# LeoBlinky2018.net
KiCad netlist of a schematic drawn in Altium Designer
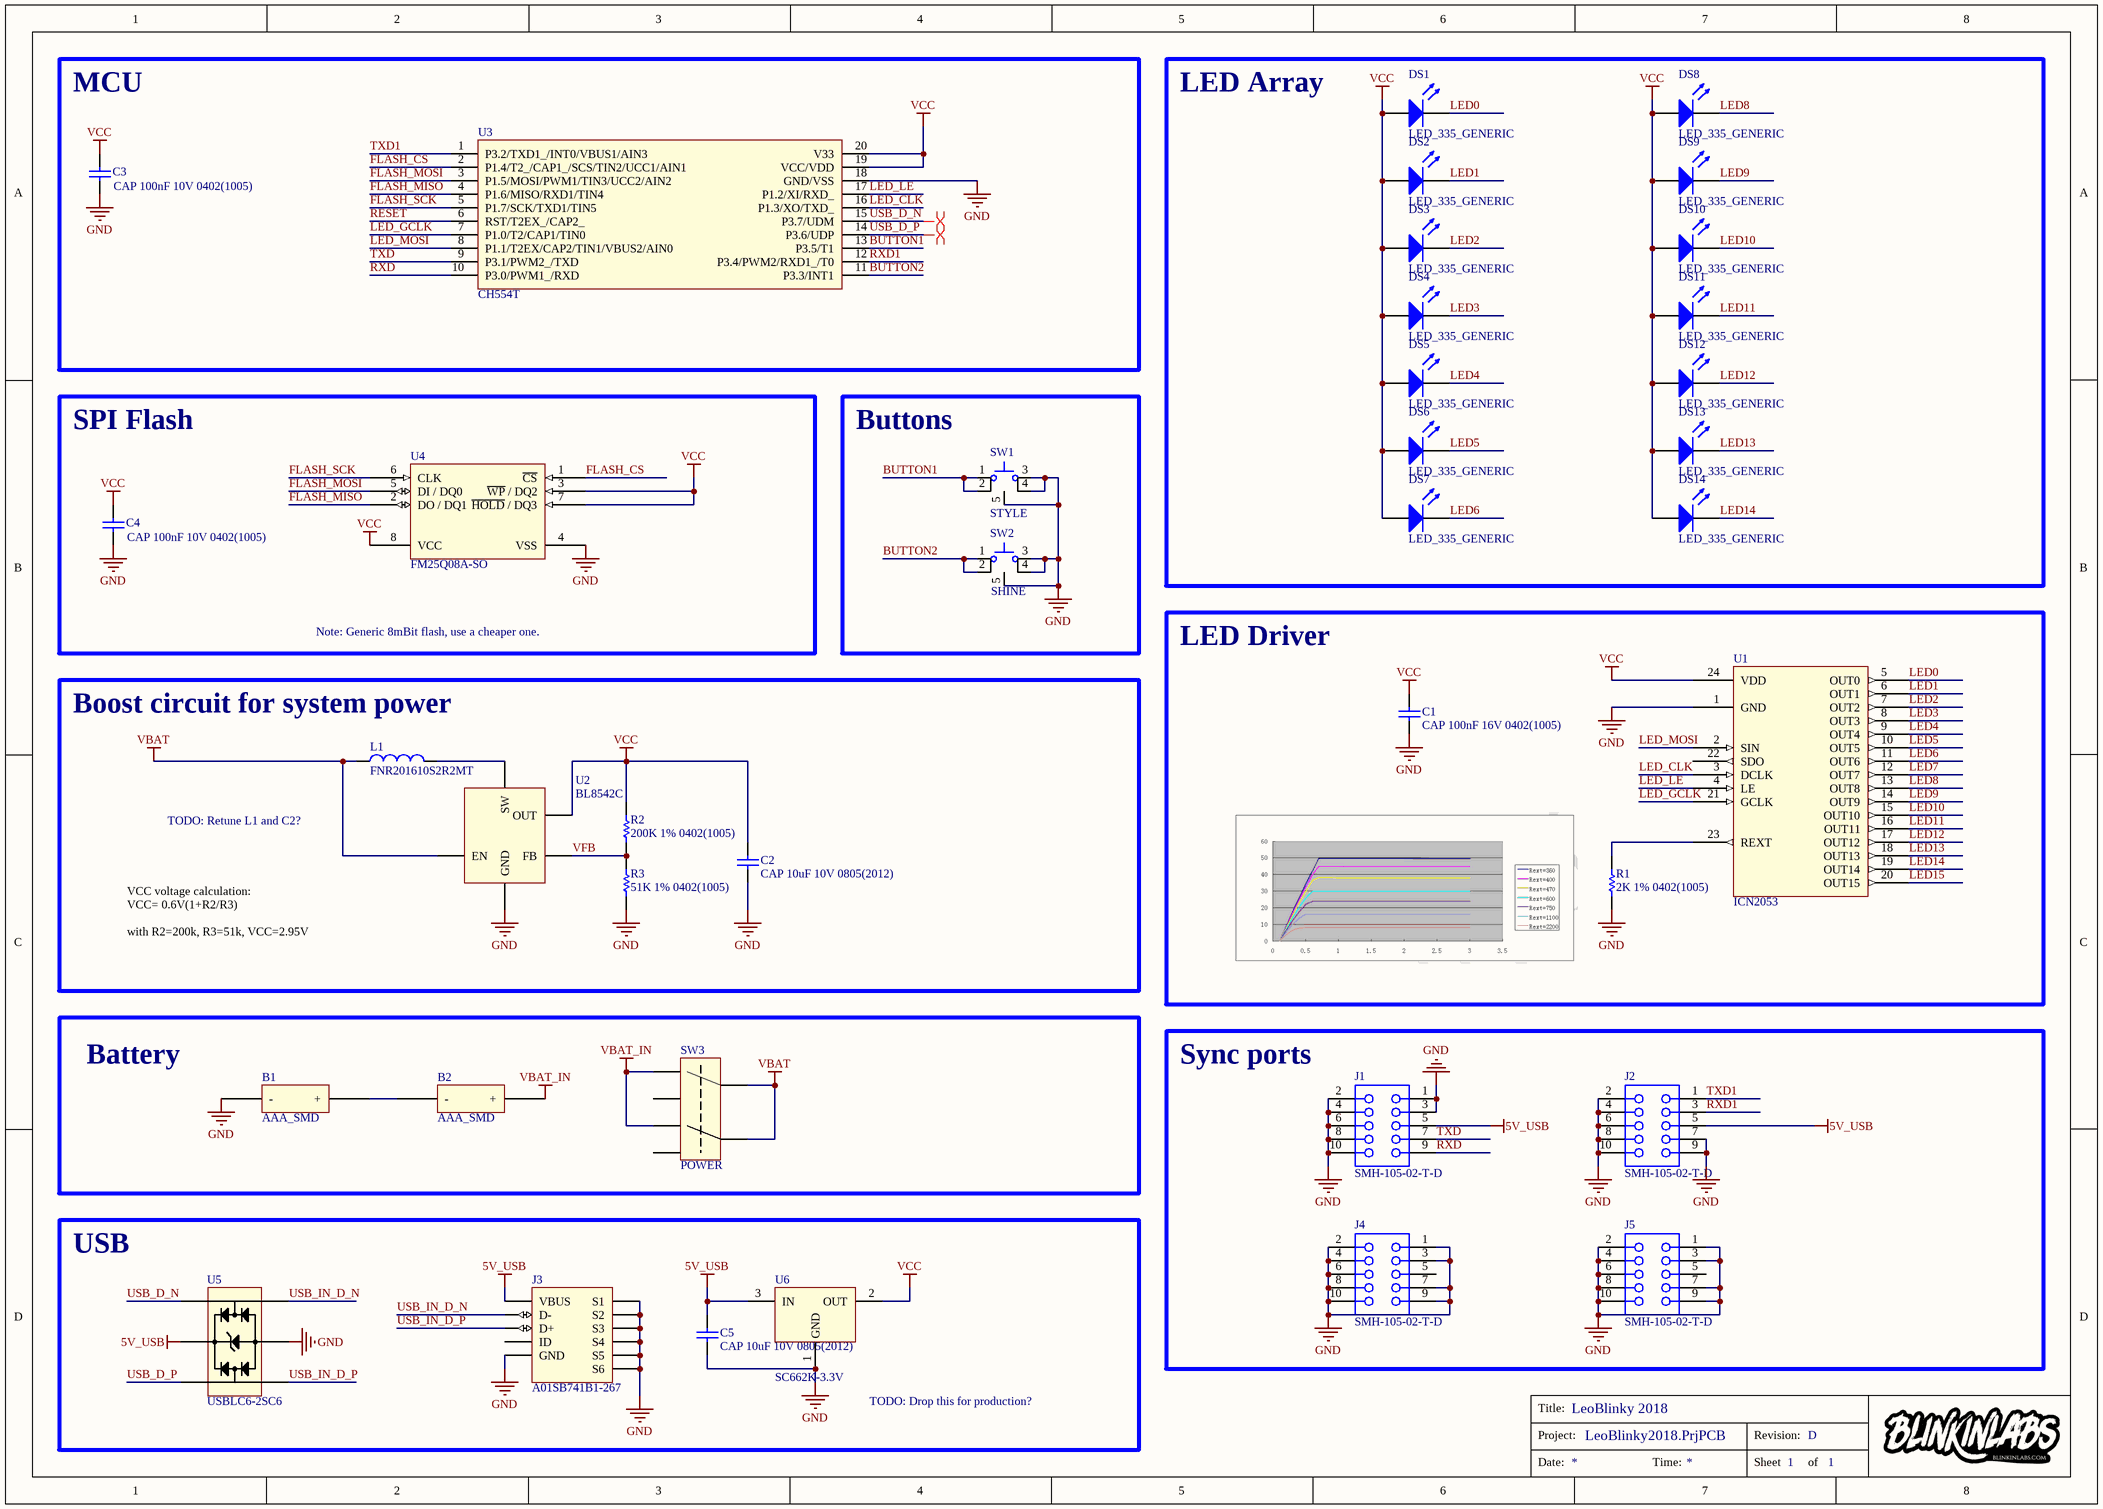
[diagram p0: LeoBlinky2018.SchDoc]

(export (version "E")
  (design (tool "Eeschema 10.0.6"))
  (components
    (comp (ref "B1")
      (value "AAA_SMD")
      (footprint "AAA_SMD")
      (description "AAA battery holder, surface mount.")
      (libsource (lib "Blinkinlabs") (part "AAA_SMD"))
    )
    (comp (ref "B2")
      (value "AAA_SMD")
      (footprint "AAA_SMD")
      (description "AAA battery holder, surface mount.")
      (libsource (lib "Blinkinlabs") (part "AAA_SMD"))
    )
    (comp (ref "C1")
      (value "CAP 100nF 16V 0402(1005)")
      (footprint "CAPC0402(1005)60_N")
      (description "CAP 100nF 16V -20% to +80% 0402 (1005 Metric) Thickness 0.6mm SMD")
      (fields (field (name "TOLERANCE") "-20% to +80%"))
      (libsource (lib "Altium Content Vault") (part "CAP"))
    )
    (comp (ref "C2")
      (value "CAP 10uF 10V 0805(2012)")
      (footprint "CAPC0805(2012)145_N")
      (description "CAP 10uF 10V ±10% 0805 (2012 Metric) Thickness 1.45mm SMD")
      (fields (field (name "TOLERANCE") "Â±10%"))
      (libsource (lib "Altium Content Vault") (part "CMP-1036-04922-1"))
    )
    (comp (ref "C3")
      (value "CAP 100nF 10V 0402(1005)")
      (footprint "CAPC0402(1005)60_L")
      (description "CAP 100nF 10V ±10% 0402 (1005 Metric) Thickness 0.6mm SMD")
      (fields (field (name "TOLERANCE") "Â±10%"))
      (libsource (lib "Altium Content Vault") (part "CMP-1034-02065-1"))
    )
    (comp (ref "C4")
      (value "CAP 100nF 10V 0402(1005)")
      (footprint "CAPC0402(1005)60_L")
      (description "CAP 100nF 10V ±10% 0402 (1005 Metric) Thickness 0.6mm SMD")
      (fields (field (name "TOLERANCE") "Â±10%"))
      (libsource (lib "Altium Content Vault") (part "CMP-1034-02065-1"))
    )
    (comp (ref "C5")
      (value "CAP 10uF 10V 0805(2012)")
      (footprint "CAPC0805(2012)145_N")
      (description "CAP 10uF 10V ±10% 0805 (2012 Metric) Thickness 1.45mm SMD")
      (fields (field (name "TOLERANCE") "Â±10%"))
      (libsource (lib "Altium Content Vault") (part "CAP"))
    )
    (comp (ref "DS1")
      (value "LED_335_GENERIC")
      (footprint "LED_335_GENERIC")
      (description "SMD LED, side visible, generic")
      (libsource (lib "Blinkinlabs") (part "LED_335_GENERIC"))
    )
    (comp (ref "DS2")
      (value "LED_335_GENERIC")
      (footprint "LED_335_GENERIC")
      (description "SMD LED, side visible, generic")
      (libsource (lib "Blinkinlabs") (part "LED_335_GENERIC"))
    )
    (comp (ref "DS3")
      (value "LED_335_GENERIC")
      (footprint "LED_335_GENERIC")
      (description "SMD LED, side visible, generic")
      (libsource (lib "Blinkinlabs") (part "LED_335_GENERIC"))
    )
    (comp (ref "DS4")
      (value "LED_335_GENERIC")
      (footprint "LED_335_GENERIC")
      (description "SMD LED, side visible, generic")
      (libsource (lib "Blinkinlabs") (part "LED_335_GENERIC"))
    )
    (comp (ref "DS5")
      (value "LED_335_GENERIC")
      (footprint "LED_335_GENERIC")
      (description "SMD LED, side visible, generic")
      (libsource (lib "Blinkinlabs") (part "LED_335_GENERIC"))
    )
    (comp (ref "DS6")
      (value "LED_335_GENERIC")
      (footprint "LED_335_GENERIC")
      (description "SMD LED, side visible, generic")
      (libsource (lib "Blinkinlabs") (part "LED_335_GENERIC"))
    )
    (comp (ref "DS7")
      (value "LED_335_GENERIC")
      (footprint "LED_335_GENERIC")
      (description "SMD LED, side visible, generic")
      (libsource (lib "Blinkinlabs") (part "LED_335_GENERIC"))
    )
    (comp (ref "DS8")
      (value "LED_335_GENERIC")
      (footprint "LED_335_GENERIC")
      (description "SMD LED, side visible, generic")
      (libsource (lib "Blinkinlabs") (part "LED_335_GENERIC"))
    )
    (comp (ref "DS9")
      (value "LED_335_GENERIC")
      (footprint "LED_335_GENERIC")
      (description "SMD LED, side visible, generic")
      (libsource (lib "Blinkinlabs") (part "LED_335_GENERIC"))
    )
    (comp (ref "DS10")
      (value "LED_335_GENERIC")
      (footprint "LED_335_GENERIC")
      (description "SMD LED, side visible, generic")
      (libsource (lib "Blinkinlabs") (part "LED_335_GENERIC"))
    )
    (comp (ref "DS11")
      (value "LED_335_GENERIC")
      (footprint "LED_335_GENERIC")
      (description "SMD LED, side visible, generic")
      (libsource (lib "Blinkinlabs") (part "LED_335_GENERIC"))
    )
    (comp (ref "DS12")
      (value "LED_335_GENERIC")
      (footprint "LED_335_GENERIC")
      (description "SMD LED, side visible, generic")
      (libsource (lib "Blinkinlabs") (part "LED_335_GENERIC"))
    )
    (comp (ref "DS13")
      (value "LED_335_GENERIC")
      (footprint "LED_335_GENERIC")
      (description "SMD LED, side visible, generic")
      (libsource (lib "Blinkinlabs") (part "LED_335_GENERIC"))
    )
    (comp (ref "DS14")
      (value "LED_335_GENERIC")
      (footprint "LED_335_GENERIC")
      (description "SMD LED, side visible, generic")
      (libsource (lib "Blinkinlabs") (part "LED_335_GENERIC"))
    )
    (comp (ref "J1")
      (value "SMH-105-02-T-D")
      (footprint "SMTC-SMH-105-02-X-D")
      (description "SMT Horizontal Socket, -55 to 105 degC, 2.54 mm Pitch, 10-Pin, Female, RoHS")
      (fields (field (name "MANUFACTURER") "Samtec"))
      (libsource (lib "Altium Content Vault") (part "SMTC-SMH-105-02-X-D-X"))
    )
    (comp (ref "J2")
      (value "SMH-105-02-T-D")
      (footprint "SMTC-SMH-105-02-X-D")
      (description "SMT Horizontal Socket, -55 to 105 degC, 2.54 mm Pitch, 10-Pin, Female, RoHS")
      (fields (field (name "MANUFACTURER") "Samtec"))
      (libsource (lib "Altium Content Vault") (part "SMTC-SMH-105-02-X-D-X"))
    )
    (comp (ref "J3")
      (value "A01SB741B1-267")
      (footprint "A01SB741B1-267")
      (description "Micro USB B type 四脚全插牛角")
      (libsource (lib "Blinkinlabs") (part "A01SB741B1-267"))
    )
    (comp (ref "J4")
      (value "SMH-105-02-T-D")
      (footprint "SMTC-SMH-105-02-X-D")
      (description "SMT Horizontal Socket, -55 to 105 degC, 2.54 mm Pitch, 10-Pin, Female, RoHS")
      (fields (field (name "MANUFACTURER") "Samtec"))
      (libsource (lib "Altium Content Vault") (part "SMTC-SMH-105-02-X-D-X"))
    )
    (comp (ref "J5")
      (value "SMH-105-02-T-D")
      (footprint "SMTC-SMH-105-02-X-D")
      (description "SMT Horizontal Socket, -55 to 105 degC, 2.54 mm Pitch, 10-Pin, Female, RoHS")
      (fields (field (name "MANUFACTURER") "Samtec"))
      (libsource (lib "Altium Content Vault") (part "SMTC-SMH-105-02-X-D-X"))
    )
    (comp (ref "L1")
      (value "FNR201610S2R2MT")
      (footprint "FNR201610S")
      (description "Wire Wound SMD Power Inductors 2.0×1.6×1.0 2.2uH")
      (libsource (lib "Blinkinlabs") (part "FNR201610S2R2MT"))
    )
    (comp (ref "R1")
      (value "2K 1% 0402(1005)")
      (footprint "RESC0402(1005)_N")
      (description "2K 0.063W 1% 0402 (1005 Metric)  SMD")
      (fields (field (name "POWER") "0.063 W") (field (name "TOLERANCE") "1 %"))
      (libsource (lib "Altium Content Vault") (part "RES"))
    )
    (comp (ref "R2")
      (value "200K 1% 0402(1005)")
      (footprint "RESC0402(1005)_L")
      (description "200K 0.063W 1% 0402 (1005 Metric)  SMD")
      (fields (field (name "TOLERANCE") "1 %") (field (name "POWER") "0.063 W"))
      (libsource (lib "Altium Content Vault") (part "RES"))
    )
    (comp (ref "R3")
      (value "51K 1% 0402(1005)")
      (footprint "RESC0402(1005)_L")
      (description "51K 0.063W 1% 0402 (1005 Metric)  SMD")
      (fields (field (name "TOLERANCE") "1 %") (field (name "POWER") "0.063 W"))
      (libsource (lib "Altium Content Vault") (part "RES"))
    )
    (comp (ref "SW1")
      (value "STYLE")
      (footprint "TD-07XB")
      (description "Tact Switch")
      (fields
        (field (name "MANUFACTURER") "ShenZhen XieJia Electronics Co Ltd")
        (field (name "PARTNUMBER") "TD-07XB")
      )
      (libsource (lib "Blinkinlabs") (part "TD-07XB"))
    )
    (comp (ref "SW2")
      (value "SHINE")
      (footprint "TD-07XB")
      (description "Tact Switch")
      (fields
        (field (name "MANUFACTURER") "ShenZhen XieJia Electronics Co Ltd")
        (field (name "PARTNUMBER") "TD-07XB")
      )
      (libsource (lib "Blinkinlabs") (part "TD-07XB"))
    )
    (comp (ref "SW3")
      (value "POWER")
      (footprint "MSK-1133-NOHOLE")
      (description "SMD micro toggle switch, 2 position, 2 circuit")
      (libsource (lib "Blinkinlabs") (part "MSK-1133"))
    )
    (comp (ref "U1")
      (value "ICN2053")
      (footprint "SOP64P600X175-24N")
      (description "16-Channel PWM Constant Current LED Sink Driver")
      (fields (field (name "MANUFACTURER") "ChipOne"))
      (libsource (lib "Blinkinlabs") (part "ICN2053"))
    )
    (comp (ref "U2")
      (value "BL8542C")
      (footprint "SOT95P280X130-5N")
      (description "0.85V startup, 1MHz, 300mA Iout,  Synchronous Boost Converter (adjustable output)")
      (fields (field (name "MANUFACTURER") "Belling"))
      (libsource (lib "Blinkinlabs") (part "BL8542C"))
    )
    (comp (ref "U3")
      (value "CH554T")
      (footprint "TSOP65P660X110-20N")
      (description "8-bit enhanced USB microcontroller")
      (fields (field (name "MANUFACTURER") "WCH"))
      (libsource (lib "Blinkinlabs") (part "CH554T"))
    )
    (comp (ref "U4")
      (value "FM25Q08A-SO")
      (footprint "SOP127P600X175-8N")
      (description "8M-BIT SERIAL FLASH MEMORY, 150mil width")
      (fields (field (name "MANUFACTURER") "Shanghai Fudan Microelectronics Group Company Limited"))
      (libsource (lib "Blinkinlabs") (part "FM25Q08A-SO"))
    )
    (comp (ref "U5")
      (value "USBLC6-2SC6")
      (footprint "SOT95P280X145-6N")
      (description "Very low capacitance ESD protection")
      (fields (field (name "MANUFACTURER") "STMicroelectronics"))
      (libsource (lib "Blinkinlabs") (part "USBLC6-2SC6"))
    )
    (comp (ref "U6")
      (value "SC662K-3.3V")
      (footprint "SOT95P230X117-3N")
      (description "3.3V, 250mA Low dropout voltage regulator IC")
      (libsource (lib "Blinkinlabs") (part "SC662K-3.3V"))
    )
  )
  (nets
    (net (code "1") (name "/BUTTON1") (class "Default")
      (node (ref "SW1") (pin "1") (pinfunction "1_1") (pintype "passive"))
      (node (ref "SW1") (pin "2") (pinfunction "2_2") (pintype "passive"))
      (node (ref "U3") (pin "13") (pinfunction "P3.5/T1_13") (pintype "passive"))
    )
    (net (code "2") (name "/BUTTON2") (class "Default")
      (node (ref "SW2") (pin "1") (pinfunction "1_1") (pintype "passive"))
      (node (ref "SW2") (pin "2") (pinfunction "2_2") (pintype "passive"))
      (node (ref "U3") (pin "11") (pinfunction "P3.3/INT1_11") (pintype "passive"))
    )
    (net (code "3") (name "/FLASH_CS") (class "Default")
      (node (ref "U3") (pin "2") (pinfunction "P1.4/T2_/CAP1_/SCS/TIN2/UCC1/AIN1_2") (pintype "passive"))
      (node (ref "U4") (pin "1") (pinfunction "~{CS}_1") (pintype "input"))
    )
    (net (code "4") (name "/FLASH_MISO") (class "Default")
      (node (ref "U3") (pin "4") (pinfunction "P1.6/MISO/RXD1/TIN4_4") (pintype "passive"))
      (node (ref "U4") (pin "2") (pinfunction "DO_/_DQ1_2") (pintype "bidirectional"))
    )
    (net (code "5") (name "/FLASH_MOSI") (class "Default")
      (node (ref "U3") (pin "3") (pinfunction "P1.5/MOSI/PWM1/TIN3/UCC2/AIN2_3") (pintype "passive"))
      (node (ref "U4") (pin "5") (pinfunction "DI_/_DQ0_5") (pintype "bidirectional"))
    )
    (net (code "6") (name "/FLASH_SCK") (class "Default")
      (node (ref "U3") (pin "5") (pinfunction "P1.7/SCK/TXD1/TIN5_5") (pintype "passive"))
      (node (ref "U4") (pin "6") (pinfunction "CLK_6") (pintype "input"))
    )
    (net (code "7") (name "/LED0") (class "Default")
      (node (ref "DS1") (pin "1") (pinfunction "1_1") (pintype "passive"))
      (node (ref "U1") (pin "5") (pinfunction "OUT0_5") (pintype "output"))
    )
    (net (code "8") (name "/LED1") (class "Default")
      (node (ref "DS2") (pin "1") (pinfunction "1_1") (pintype "passive"))
      (node (ref "U1") (pin "6") (pinfunction "OUT1_6") (pintype "output"))
    )
    (net (code "9") (name "/LED2") (class "Default")
      (node (ref "DS3") (pin "1") (pinfunction "1_1") (pintype "passive"))
      (node (ref "U1") (pin "7") (pinfunction "OUT2_7") (pintype "output"))
    )
    (net (code "10") (name "/LED3") (class "Default")
      (node (ref "DS4") (pin "1") (pinfunction "1_1") (pintype "passive"))
      (node (ref "U1") (pin "8") (pinfunction "OUT3_8") (pintype "output"))
    )
    (net (code "11") (name "/LED4") (class "Default")
      (node (ref "DS5") (pin "1") (pinfunction "1_1") (pintype "passive"))
      (node (ref "U1") (pin "9") (pinfunction "OUT4_9") (pintype "output"))
    )
    (net (code "12") (name "/LED5") (class "Default")
      (node (ref "DS6") (pin "1") (pinfunction "1_1") (pintype "passive"))
      (node (ref "U1") (pin "10") (pinfunction "OUT5_10") (pintype "output"))
    )
    (net (code "13") (name "/LED6") (class "Default")
      (node (ref "DS7") (pin "1") (pinfunction "1_1") (pintype "passive"))
      (node (ref "U1") (pin "11") (pinfunction "OUT6_11") (pintype "output"))
    )
    (net (code "14") (name "/LED7") (class "Default")
      (node (ref "U1") (pin "12") (pinfunction "OUT7_12") (pintype "output"))
    )
    (net (code "15") (name "/LED8") (class "Default")
      (node (ref "DS8") (pin "1") (pinfunction "1_1") (pintype "passive"))
      (node (ref "U1") (pin "13") (pinfunction "OUT8_13") (pintype "output"))
    )
    (net (code "16") (name "/LED9") (class "Default")
      (node (ref "DS9") (pin "1") (pinfunction "1_1") (pintype "passive"))
      (node (ref "U1") (pin "14") (pinfunction "OUT9_14") (pintype "output"))
    )
    (net (code "17") (name "/LED10") (class "Default")
      (node (ref "DS10") (pin "1") (pinfunction "1_1") (pintype "passive"))
      (node (ref "U1") (pin "15") (pinfunction "OUT10_15") (pintype "output"))
    )
    (net (code "18") (name "/LED11") (class "Default")
      (node (ref "DS11") (pin "1") (pinfunction "1_1") (pintype "passive"))
      (node (ref "U1") (pin "16") (pinfunction "OUT11_16") (pintype "output"))
    )
    (net (code "19") (name "/LED12") (class "Default")
      (node (ref "DS12") (pin "1") (pinfunction "1_1") (pintype "passive"))
      (node (ref "U1") (pin "17") (pinfunction "OUT12_17") (pintype "output"))
    )
    (net (code "20") (name "/LED13") (class "Default")
      (node (ref "DS13") (pin "1") (pinfunction "1_1") (pintype "passive"))
      (node (ref "U1") (pin "18") (pinfunction "OUT13_18") (pintype "output"))
    )
    (net (code "21") (name "/LED14") (class "Default")
      (node (ref "DS14") (pin "1") (pinfunction "1_1") (pintype "passive"))
      (node (ref "U1") (pin "19") (pinfunction "OUT14_19") (pintype "output"))
    )
    (net (code "22") (name "/LED15") (class "Default")
      (node (ref "U1") (pin "20") (pinfunction "OUT15_20") (pintype "output"))
    )
    (net (code "23") (name "/LED_CLK") (class "Default")
      (node (ref "U1") (pin "3") (pinfunction "DCLK_3") (pintype "input"))
      (node (ref "U3") (pin "16") (pinfunction "P1.3/XO/TXD__16") (pintype "passive"))
    )
    (net (code "24") (name "/LED_GCLK") (class "Default")
      (node (ref "U1") (pin "21") (pinfunction "GCLK_21") (pintype "input"))
      (node (ref "U3") (pin "7") (pinfunction "P1.0/T2/CAP1/TIN0_7") (pintype "passive"))
    )
    (net (code "25") (name "/LED_LE") (class "Default")
      (node (ref "U1") (pin "4") (pinfunction "LE_4") (pintype "input"))
      (node (ref "U3") (pin "17") (pinfunction "P1.2/XI/RXD__17") (pintype "passive"))
    )
    (net (code "26") (name "/LED_MOSI") (class "Default")
      (node (ref "U1") (pin "2") (pinfunction "SIN_2") (pintype "input"))
      (node (ref "U3") (pin "8") (pinfunction "P1.1/T2EX/CAP2/TIN1/VBUS2/AIN0_8") (pintype "passive"))
    )
    (net (code "27") (name "/RESET") (class "Default")
      (node (ref "U3") (pin "6") (pinfunction "RST/T2EX_/CAP2__6") (pintype "passive"))
    )
    (net (code "28") (name "/RXD") (class "Default")
      (node (ref "J1") (pin "9") (pinfunction "9_9") (pintype "passive"))
      (node (ref "U3") (pin "10") (pinfunction "P3.0/PWM1_/RXD_10") (pintype "passive"))
    )
    (net (code "29") (name "/RXD1") (class "Default")
      (node (ref "J2") (pin "3") (pinfunction "3_3") (pintype "passive"))
      (node (ref "U3") (pin "12") (pinfunction "P3.4/PWM2/RXD1_/T0_12") (pintype "passive"))
    )
    (net (code "30") (name "/TXD") (class "Default")
      (node (ref "J1") (pin "7") (pinfunction "7_7") (pintype "passive"))
      (node (ref "U3") (pin "9") (pinfunction "P3.1/PWM2_/TXD_9") (pintype "passive"))
    )
    (net (code "31") (name "/TXD1") (class "Default")
      (node (ref "J2") (pin "1") (pinfunction "1_1") (pintype "passive"))
      (node (ref "U3") (pin "1") (pinfunction "P3.2/TXD1_/INT0/VBUS1/AIN3_1") (pintype "passive"))
    )
    (net (code "32") (name "/USB_D_N") (class "Default")
      (node (ref "U3") (pin "15") (pinfunction "P3.7/UDM_15") (pintype "passive"))
      (node (ref "U5") (pin "4") (pinfunction "I/O2_4") (pintype "passive"))
    )
    (net (code "33") (name "/USB_D_P") (class "Default")
      (node (ref "U3") (pin "14") (pinfunction "P3.6/UDP_14") (pintype "passive"))
      (node (ref "U5") (pin "6") (pinfunction "I/O1_6") (pintype "passive"))
    )
    (net (code "34") (name "/USB_IN_D_N") (class "Default")
      (node (ref "J3") (pin "D-") (pinfunction "D-_D-") (pintype "bidirectional"))
      (node (ref "U5") (pin "3") (pinfunction "I/O2_3") (pintype "passive"))
    )
    (net (code "35") (name "/USB_IN_D_P") (class "Default")
      (node (ref "J3") (pin "D+") (pinfunction "D+_D+") (pintype "bidirectional"))
      (node (ref "U5") (pin "1") (pinfunction "I/O1_1") (pintype "passive"))
    )
    (net (code "36") (name "/VFB") (class "Default")
      (node (ref "R2") (pin "1") (pinfunction "1_1") (pintype "passive"))
      (node (ref "R3") (pin "2") (pinfunction "2_2") (pintype "passive"))
      (node (ref "U2") (pin "1") (pinfunction "FB_1") (pintype "passive"))
    )
    (net (code "37") (name "5V_USB") (class "Default")
      (node (ref "C5") (pin "2") (pinfunction "2_2") (pintype "passive"))
      (node (ref "J1") (pin "5") (pinfunction "5_5") (pintype "passive"))
      (node (ref "J2") (pin "5") (pinfunction "5_5") (pintype "passive"))
      (node (ref "J3") (pin "VBUS") (pinfunction "VBUS_VBUS") (pintype "power_in"))
      (node (ref "U5") (pin "5") (pinfunction "5_5") (pintype "passive"))
      (node (ref "U6") (pin "3") (pinfunction "IN_3") (pintype "power_in"))
    )
    (net (code "38") (name "GND") (class "Default")
      (node (ref "B1") (pin "2") (pinfunction "-_2") (pintype "power_in"))
      (node (ref "C1") (pin "1") (pinfunction "1_1") (pintype "passive"))
      (node (ref "C2") (pin "1") (pinfunction "1_1") (pintype "passive"))
      (node (ref "C3") (pin "1") (pinfunction "1_1") (pintype "passive"))
      (node (ref "C4") (pin "1") (pinfunction "1_1") (pintype "passive"))
      (node (ref "C5") (pin "1") (pinfunction "1_1") (pintype "passive"))
      (node (ref "J1") (pin "1") (pinfunction "1_1") (pintype "passive"))
      (node (ref "J1") (pin "10") (pinfunction "10_10") (pintype "passive"))
      (node (ref "J1") (pin "2") (pinfunction "2_2") (pintype "passive"))
      (node (ref "J1") (pin "3") (pinfunction "3_3") (pintype "passive"))
      (node (ref "J1") (pin "4") (pinfunction "4_4") (pintype "passive"))
      (node (ref "J1") (pin "6") (pinfunction "6_6") (pintype "passive"))
      (node (ref "J1") (pin "8") (pinfunction "8_8") (pintype "passive"))
      (node (ref "J2") (pin "10") (pinfunction "10_10") (pintype "passive"))
      (node (ref "J2") (pin "2") (pinfunction "2_2") (pintype "passive"))
      (node (ref "J2") (pin "4") (pinfunction "4_4") (pintype "passive"))
      (node (ref "J2") (pin "6") (pinfunction "6_6") (pintype "passive"))
      (node (ref "J2") (pin "7") (pinfunction "7_7") (pintype "passive"))
      (node (ref "J2") (pin "8") (pinfunction "8_8") (pintype "passive"))
      (node (ref "J2") (pin "9") (pinfunction "9_9") (pintype "passive"))
      (node (ref "J3") (pin "GND") (pinfunction "GND_GND") (pintype "power_in"))
      (node (ref "J3") (pin "S1") (pinfunction "S1_S1") (pintype "passive"))
      (node (ref "J3") (pin "S2") (pinfunction "S2_S2") (pintype "passive"))
      (node (ref "J3") (pin "S3") (pinfunction "S3_S3") (pintype "passive"))
      (node (ref "J3") (pin "S4") (pinfunction "S4_S4") (pintype "passive"))
      (node (ref "J3") (pin "S5") (pinfunction "S5_S5") (pintype "passive"))
      (node (ref "J3") (pin "S6") (pinfunction "S6_S6") (pintype "passive"))
      (node (ref "J4") (pin "1") (pinfunction "1_1") (pintype "passive"))
      (node (ref "J4") (pin "10") (pinfunction "10_10") (pintype "passive"))
      (node (ref "J4") (pin "2") (pinfunction "2_2") (pintype "passive"))
      (node (ref "J4") (pin "3") (pinfunction "3_3") (pintype "passive"))
      (node (ref "J4") (pin "4") (pinfunction "4_4") (pintype "passive"))
      (node (ref "J4") (pin "6") (pinfunction "6_6") (pintype "passive"))
      (node (ref "J4") (pin "7") (pinfunction "7_7") (pintype "passive"))
      (node (ref "J4") (pin "8") (pinfunction "8_8") (pintype "passive"))
      (node (ref "J4") (pin "9") (pinfunction "9_9") (pintype "passive"))
      (node (ref "J5") (pin "1") (pinfunction "1_1") (pintype "passive"))
      (node (ref "J5") (pin "10") (pinfunction "10_10") (pintype "passive"))
      (node (ref "J5") (pin "2") (pinfunction "2_2") (pintype "passive"))
      (node (ref "J5") (pin "3") (pinfunction "3_3") (pintype "passive"))
      (node (ref "J5") (pin "4") (pinfunction "4_4") (pintype "passive"))
      (node (ref "J5") (pin "6") (pinfunction "6_6") (pintype "passive"))
      (node (ref "J5") (pin "7") (pinfunction "7_7") (pintype "passive"))
      (node (ref "J5") (pin "8") (pinfunction "8_8") (pintype "passive"))
      (node (ref "J5") (pin "9") (pinfunction "9_9") (pintype "passive"))
      (node (ref "R1") (pin "1") (pinfunction "1_1") (pintype "passive"))
      (node (ref "R3") (pin "1") (pinfunction "1_1") (pintype "passive"))
      (node (ref "SW1") (pin "3") (pinfunction "3_3") (pintype "passive"))
      (node (ref "SW1") (pin "4") (pinfunction "4_4") (pintype "passive"))
      (node (ref "SW1") (pin "5") (pinfunction "5_5") (pintype "passive"))
      (node (ref "SW2") (pin "3") (pinfunction "3_3") (pintype "passive"))
      (node (ref "SW2") (pin "4") (pinfunction "4_4") (pintype "passive"))
      (node (ref "SW2") (pin "5") (pinfunction "5_5") (pintype "passive"))
      (node (ref "U1") (pin "1") (pinfunction "GND_1") (pintype "power_in"))
      (node (ref "U2") (pin "2") (pinfunction "GND_2") (pintype "passive"))
      (node (ref "U3") (pin "18") (pinfunction "GND/VSS_18") (pintype "power_in"))
      (node (ref "U4") (pin "4") (pinfunction "VSS_4") (pintype "power_in"))
      (node (ref "U5") (pin "2") (pinfunction "GND_2") (pintype "passive"))
      (node (ref "U6") (pin "1") (pinfunction "GND_1") (pintype "power_in"))
    )
    (net (code "39") (name "Net-(B1-+)") (class "Default")
      (node (ref "B1") (pin "1") (pinfunction "+_1") (pintype "power_in"))
      (node (ref "B2") (pin "2") (pinfunction "-_2") (pintype "power_in"))
    )
    (net (code "40") (name "Net-(U1-REXT)") (class "Default")
      (node (ref "R1") (pin "2") (pinfunction "2_2") (pintype "passive"))
      (node (ref "U1") (pin "23") (pinfunction "REXT_23") (pintype "output"))
    )
    (net (code "41") (name "Net-(U2-SW)") (class "Default")
      (node (ref "L1") (pin "2") (pinfunction "2_2") (pintype "passive"))
      (node (ref "U2") (pin "4") (pinfunction "SW_4") (pintype "passive"))
    )
    (net (code "42") (name "VBAT") (class "Default")
      (node (ref "L1") (pin "1") (pinfunction "1_1") (pintype "passive"))
      (node (ref "SW3") (pin "2") (pintype "passive"))
      (node (ref "SW3") (pin "5") (pintype "passive"))
      (node (ref "U2") (pin "3") (pinfunction "EN_3") (pintype "passive"))
    )
    (net (code "43") (name "VBAT_IN") (class "Default")
      (node (ref "B2") (pin "1") (pinfunction "+_1") (pintype "power_in"))
      (node (ref "SW3") (pin "1") (pinfunction "A_1") (pintype "passive"))
      (node (ref "SW3") (pin "6") (pintype "passive"))
    )
    (net (code "44") (name "VCC") (class "Default")
      (node (ref "C1") (pin "2") (pinfunction "2_2") (pintype "passive"))
      (node (ref "C2") (pin "2") (pinfunction "2_2") (pintype "passive"))
      (node (ref "C3") (pin "2") (pinfunction "2_2") (pintype "passive"))
      (node (ref "C4") (pin "2") (pinfunction "2_2") (pintype "passive"))
      (node (ref "DS1") (pin "2") (pinfunction "1_2") (pintype "passive"))
      (node (ref "DS10") (pin "2") (pinfunction "1_2") (pintype "passive"))
      (node (ref "DS11") (pin "2") (pinfunction "1_2") (pintype "passive"))
      (node (ref "DS12") (pin "2") (pinfunction "1_2") (pintype "passive"))
      (node (ref "DS13") (pin "2") (pinfunction "1_2") (pintype "passive"))
      (node (ref "DS14") (pin "2") (pinfunction "1_2") (pintype "passive"))
      (node (ref "DS2") (pin "2") (pinfunction "1_2") (pintype "passive"))
      (node (ref "DS3") (pin "2") (pinfunction "1_2") (pintype "passive"))
      (node (ref "DS4") (pin "2") (pinfunction "1_2") (pintype "passive"))
      (node (ref "DS5") (pin "2") (pinfunction "1_2") (pintype "passive"))
      (node (ref "DS6") (pin "2") (pinfunction "1_2") (pintype "passive"))
      (node (ref "DS7") (pin "2") (pinfunction "1_2") (pintype "passive"))
      (node (ref "DS8") (pin "2") (pinfunction "1_2") (pintype "passive"))
      (node (ref "DS9") (pin "2") (pinfunction "1_2") (pintype "passive"))
      (node (ref "R2") (pin "2") (pinfunction "2_2") (pintype "passive"))
      (node (ref "U1") (pin "24") (pinfunction "VDD_24") (pintype "power_in"))
      (node (ref "U2") (pin "5") (pinfunction "OUT_5") (pintype "passive"))
      (node (ref "U3") (pin "19") (pinfunction "VCC/VDD_19") (pintype "power_in"))
      (node (ref "U3") (pin "20") (pinfunction "V33_20") (pintype "power_in"))
      (node (ref "U4") (pin "3") (pinfunction "~{WP}_/_DQ2_3") (pintype "input"))
      (node (ref "U4") (pin "7") (pinfunction "~{HOLD}_/_DQ3_7") (pintype "input"))
      (node (ref "U4") (pin "8") (pinfunction "VCC_8") (pintype "power_in"))
      (node (ref "U6") (pin "2") (pinfunction "OUT_2") (pintype "power_in"))
    )
    (net (code "45") (name "unconnected-(J3-PadID)") (class "Default")
      (node (ref "J3") (pin "ID") (pinfunction "ID_ID") (pintype "passive"))
    )
    (net (code "46") (name "unconnected-(J4-Pad5)") (class "Default")
      (node (ref "J4") (pin "5") (pinfunction "5_5") (pintype "passive"))
    )
    (net (code "47") (name "unconnected-(J5-Pad5)") (class "Default")
      (node (ref "J5") (pin "5") (pinfunction "5_5") (pintype "passive"))
    )
    (net (code "48") (name "unconnected-(SW3-Pad3)") (class "Default")
      (node (ref "SW3") (pin "3") (pintype "passive"))
    )
    (net (code "49") (name "unconnected-(SW3-Pad4)") (class "Default")
      (node (ref "SW3") (pin "4") (pintype "passive"))
    )
    (net (code "50") (name "unconnected-(U1-SDO-Pad22)") (class "Default")
      (node (ref "U1") (pin "22") (pinfunction "SDO_22") (pintype "output"))
    )
  )
)
